# HHKBLite2BTwithoutArduinoFTDI.net
KiCad netlist of a schematic drawn in EAGLE
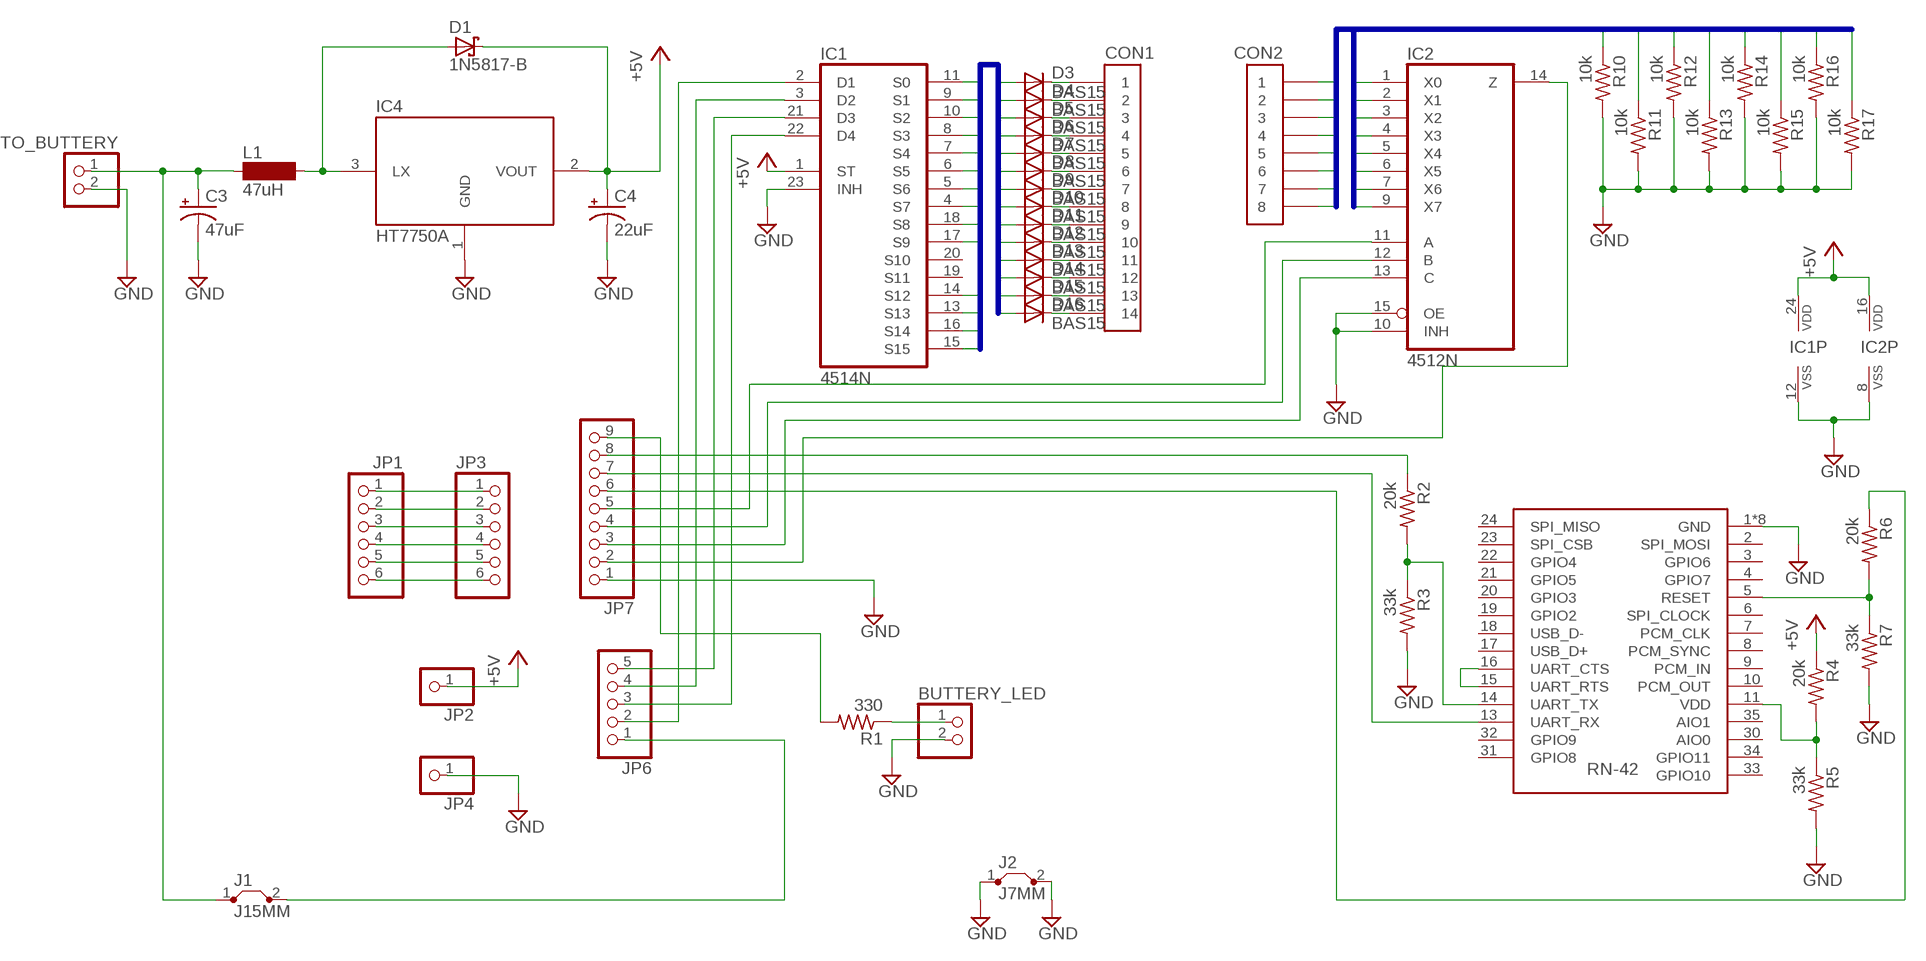
[diagram p0: schematic, sheet 1]

(export (version "E")
  (design (tool "Eeschema 10.0.6"))
  (components
    (comp (ref "BUTTERY_LED")
      (value "PINHD-1X2")
      (footprint "eagle-import:1X02")
      (libsource (lib "eagle-import") (part "PINHD-1X2"))
    )
    (comp (ref "C3")
      (value "47uF")
      (footprint "eagle-import:E5-10,5")
      (libsource (lib "eagle-import") (part "CPOL-USE5-10.5"))
    )
    (comp (ref "C4")
      (value "22uF")
      (footprint "eagle-import:E5-10,5")
      (libsource (lib "eagle-import") (part "CPOL-USE5-10.5"))
    )
    (comp (ref "CON1")
      (value "45045-1445")
      (footprint "eagle-import:52045-1445")
      (libsource (lib "eagle-import") (part "45045-1445"))
    )
    (comp (ref "CON2")
      (value "45045-0845")
      (footprint "eagle-import:52045-0845")
      (libsource (lib "eagle-import") (part "45045-0845"))
    )
    (comp (ref "D1")
      (value "1N5817-B")
      (footprint "eagle-import:DO41-7.6")
      (libsource (lib "eagle-import") (part "1N5817-B"))
    )
    (comp (ref "D3")
      (value "BAS15")
      (footprint "eagle-import:DO34-7")
      (libsource (lib "eagle-import") (part "BAS15"))
    )
    (comp (ref "D4")
      (value "BAS15")
      (footprint "eagle-import:DO34-7")
      (libsource (lib "eagle-import") (part "BAS15"))
    )
    (comp (ref "D5")
      (value "BAS15")
      (footprint "eagle-import:DO34-7")
      (libsource (lib "eagle-import") (part "BAS15"))
    )
    (comp (ref "D6")
      (value "BAS15")
      (footprint "eagle-import:DO34-7")
      (libsource (lib "eagle-import") (part "BAS15"))
    )
    (comp (ref "D7")
      (value "BAS15")
      (footprint "eagle-import:DO34-7")
      (libsource (lib "eagle-import") (part "BAS15"))
    )
    (comp (ref "D8")
      (value "BAS15")
      (footprint "eagle-import:DO34-7")
      (libsource (lib "eagle-import") (part "BAS15"))
    )
    (comp (ref "D9")
      (value "BAS15")
      (footprint "eagle-import:DO34-7")
      (libsource (lib "eagle-import") (part "BAS15"))
    )
    (comp (ref "D10")
      (value "BAS15")
      (footprint "eagle-import:DO34-7")
      (libsource (lib "eagle-import") (part "BAS15"))
    )
    (comp (ref "D11")
      (value "BAS15")
      (footprint "eagle-import:DO34-7")
      (libsource (lib "eagle-import") (part "BAS15"))
    )
    (comp (ref "D12")
      (value "BAS15")
      (footprint "eagle-import:DO34-7")
      (libsource (lib "eagle-import") (part "BAS15"))
    )
    (comp (ref "D13")
      (value "BAS15")
      (footprint "eagle-import:DO34-7")
      (libsource (lib "eagle-import") (part "BAS15"))
    )
    (comp (ref "D14")
      (value "BAS15")
      (footprint "eagle-import:DO34-7")
      (libsource (lib "eagle-import") (part "BAS15"))
    )
    (comp (ref "D15")
      (value "BAS15")
      (footprint "eagle-import:DO34-7")
      (libsource (lib "eagle-import") (part "BAS15"))
    )
    (comp (ref "D16")
      (value "BAS15")
      (footprint "eagle-import:DO34-7")
      (libsource (lib "eagle-import") (part "BAS15"))
    )
    (comp (ref "IC1")
      (value "4514N")
      (footprint "eagle-import:DIL24-6")
      (libsource (lib "eagle-import") (part "4514N"))
    )
    (comp (ref "IC2")
      (value "4512N")
      (footprint "eagle-import:DIL16")
      (libsource (lib "eagle-import") (part "4512N"))
    )
    (comp (ref "IC4")
      (value "HT7750A")
      (footprint "eagle-import:TO-92")
      (libsource (lib "eagle-import") (part "HT7750A"))
    )
    (comp (ref "J1")
      (value "J15MM")
      (footprint "eagle-import:15")
      (libsource (lib "eagle-import") (part "J15MM"))
    )
    (comp (ref "J2")
      (value "J7MM")
      (footprint "eagle-import:07")
      (libsource (lib "eagle-import") (part "J7MM"))
    )
    (comp (ref "JP1")
      (value "PINHD-1X6")
      (footprint "eagle-import:1X06")
      (libsource (lib "eagle-import") (part "PINHD-1X6"))
    )
    (comp (ref "JP2")
      (value "PINHD-1X1")
      (footprint "eagle-import:1X01")
      (libsource (lib "eagle-import") (part "PINHD-1X1"))
    )
    (comp (ref "JP3")
      (value "PINHD-1X6/90")
      (footprint "eagle-import:1X06_90")
      (libsource (lib "eagle-import") (part "PINHD-1X6/90"))
    )
    (comp (ref "JP4")
      (value "PINHD-1X1")
      (footprint "eagle-import:1X01")
      (libsource (lib "eagle-import") (part "PINHD-1X1"))
    )
    (comp (ref "JP6")
      (value "PINHD-1X5")
      (footprint "eagle-import:1X05")
      (libsource (lib "eagle-import") (part "PINHD-1X5"))
    )
    (comp (ref "JP7")
      (value "PINHD-1X9")
      (footprint "eagle-import:1X09")
      (libsource (lib "eagle-import") (part "PINHD-1X9"))
    )
    (comp (ref "L1")
      (value "47uH")
      (footprint "eagle-import:BS11")
      (libsource (lib "eagle-import") (part "BS11"))
    )
    (comp (ref "R1")
      (value "330")
      (footprint "eagle-import:0207_7")
      (libsource (lib "eagle-import") (part "R-US_0207/7"))
    )
    (comp (ref "R2")
      (value "20k")
      (footprint "eagle-import:0207_7")
      (libsource (lib "eagle-import") (part "R-US_0207/7"))
    )
    (comp (ref "R3")
      (value "33k")
      (footprint "eagle-import:0207_7")
      (libsource (lib "eagle-import") (part "R-US_0207/7"))
    )
    (comp (ref "R4")
      (value "20k")
      (footprint "eagle-import:0207_7")
      (libsource (lib "eagle-import") (part "R-US_0207/7"))
    )
    (comp (ref "R5")
      (value "33k")
      (footprint "eagle-import:0207_7")
      (libsource (lib "eagle-import") (part "R-US_0207/7"))
    )
    (comp (ref "R6")
      (value "20k")
      (footprint "eagle-import:0207_7")
      (libsource (lib "eagle-import") (part "R-US_0207/7"))
    )
    (comp (ref "R7")
      (value "33k")
      (footprint "eagle-import:0207_7")
      (libsource (lib "eagle-import") (part "R-US_0207/7"))
    )
    (comp (ref "R10")
      (value "10k")
      (footprint "eagle-import:0207_7")
      (libsource (lib "eagle-import") (part "R-US_0207/7"))
    )
    (comp (ref "R11")
      (value "10k")
      (footprint "eagle-import:0207_7")
      (libsource (lib "eagle-import") (part "R-US_0207/7"))
    )
    (comp (ref "R12")
      (value "10k")
      (footprint "eagle-import:0207_7")
      (libsource (lib "eagle-import") (part "R-US_0207/7"))
    )
    (comp (ref "R13")
      (value "10k")
      (footprint "eagle-import:0207_10")
      (libsource (lib "eagle-import") (part "resistor_R-US_0207/10"))
    )
    (comp (ref "R14")
      (value "10k")
      (footprint "eagle-import:0207_7")
      (libsource (lib "eagle-import") (part "R-US_0207/7"))
    )
    (comp (ref "R15")
      (value "10k")
      (footprint "eagle-import:0207_7")
      (libsource (lib "eagle-import") (part "R-US_0207/7"))
    )
    (comp (ref "R16")
      (value "10k")
      (footprint "eagle-import:0207_7")
      (libsource (lib "eagle-import") (part "R-US_0207/7"))
    )
    (comp (ref "R17")
      (value "10k")
      (footprint "eagle-import:0207_7")
      (libsource (lib "eagle-import") (part "R-US_0207/7"))
    )
    (comp (ref "TO_BUTTERY")
      (value "PINHD-1X2")
      (footprint "eagle-import:1X02")
      (libsource (lib "eagle-import") (part "PINHD-1X2"))
    )
    (comp (ref "U$1")
      (value "RN-42")
      (footprint "eagle-import:RN-42")
      (libsource (lib "eagle-import") (part "RN-42"))
    )
  )
  (nets
    (net (code "1") (name "+5V") (class "Default")
      (node (ref "C4") (pin "+") (pinfunction "+_+") (pintype "passive"))
      (node (ref "D1") (pin "C") (pinfunction "C_C") (pintype "passive"))
      (node (ref "IC1") (pin "1") (pinfunction "ST_1") (pintype "input"))
      (node (ref "IC1") (pin "24") (pinfunction "VDD_24") (pintype "power_in"))
      (node (ref "IC2") (pin "16") (pinfunction "VDD_16") (pintype "power_in"))
      (node (ref "IC4") (pin "2") (pinfunction "VOUT_2") (pintype "output"))
      (node (ref "JP2") (pin "1") (pinfunction "1_1") (pintype "passive"))
      (node (ref "R4") (pin "1") (pinfunction "1_1") (pintype "passive"))
    )
    (net (code "2") (name "/CON1BUS_O0") (class "Default")
      (node (ref "D3") (pin "A") (pinfunction "A_A") (pintype "passive"))
      (node (ref "IC1") (pin "11") (pinfunction "S0_11") (pintype "output"))
    )
    (net (code "3") (name "/CON1BUS_O1") (class "Default")
      (node (ref "D5") (pin "A") (pinfunction "A_A") (pintype "passive"))
      (node (ref "IC1") (pin "9") (pinfunction "S1_9") (pintype "output"))
    )
    (net (code "4") (name "/CON1BUS_O2") (class "Default")
      (node (ref "D4") (pin "A") (pinfunction "A_A") (pintype "passive"))
      (node (ref "IC1") (pin "10") (pinfunction "S2_10") (pintype "output"))
    )
    (net (code "5") (name "/CON1BUS_O3") (class "Default")
      (node (ref "D6") (pin "A") (pinfunction "A_A") (pintype "passive"))
      (node (ref "IC1") (pin "8") (pinfunction "S3_8") (pintype "output"))
    )
    (net (code "6") (name "/CON1BUS_O4") (class "Default")
      (node (ref "D7") (pin "A") (pinfunction "A_A") (pintype "passive"))
      (node (ref "IC1") (pin "7") (pinfunction "S4_7") (pintype "output"))
    )
    (net (code "7") (name "/CON1BUS_O5") (class "Default")
      (node (ref "D8") (pin "A") (pinfunction "A_A") (pintype "passive"))
      (node (ref "IC1") (pin "6") (pinfunction "S5_6") (pintype "output"))
    )
    (net (code "8") (name "/CON1BUS_O6") (class "Default")
      (node (ref "D9") (pin "A") (pinfunction "A_A") (pintype "passive"))
      (node (ref "IC1") (pin "5") (pinfunction "S6_5") (pintype "output"))
    )
    (net (code "9") (name "/CON1BUS_O7") (class "Default")
      (node (ref "D10") (pin "A") (pinfunction "A_A") (pintype "passive"))
      (node (ref "IC1") (pin "4") (pinfunction "S7_4") (pintype "output"))
    )
    (net (code "10") (name "/CON1BUS_O8") (class "Default")
      (node (ref "D11") (pin "A") (pinfunction "A_A") (pintype "passive"))
      (node (ref "IC1") (pin "18") (pinfunction "S8_18") (pintype "output"))
    )
    (net (code "11") (name "/CON1BUS_O9") (class "Default")
      (node (ref "D16") (pin "A") (pinfunction "A_A") (pintype "passive"))
      (node (ref "IC1") (pin "17") (pinfunction "S9_17") (pintype "output"))
    )
    (net (code "12") (name "/CON1BUS_O12") (class "Default")
      (node (ref "D13") (pin "A") (pinfunction "A_A") (pintype "passive"))
      (node (ref "IC1") (pin "14") (pinfunction "S12_14") (pintype "output"))
    )
    (net (code "13") (name "/CON1BUS_O13") (class "Default")
      (node (ref "D12") (pin "A") (pinfunction "A_A") (pintype "passive"))
      (node (ref "IC1") (pin "13") (pinfunction "S13_13") (pintype "output"))
    )
    (net (code "14") (name "/CON1BUS_O14") (class "Default")
      (node (ref "D15") (pin "A") (pinfunction "A_A") (pintype "passive"))
      (node (ref "IC1") (pin "16") (pinfunction "S14_16") (pintype "output"))
    )
    (net (code "15") (name "/CON1BUS_O15") (class "Default")
      (node (ref "D14") (pin "A") (pinfunction "A_A") (pintype "passive"))
      (node (ref "IC1") (pin "15") (pinfunction "S15_15") (pintype "output"))
    )
    (net (code "16") (name "/CON2BUS_D0") (class "Default")
      (node (ref "CON2") (pin "8") (pinfunction "8_8") (pintype "bidirectional"))
      (node (ref "IC2") (pin "1") (pinfunction "X0_1") (pintype "input"))
      (node (ref "R10") (pin "1") (pinfunction "1_1") (pintype "passive"))
    )
    (net (code "17") (name "/CON2BUS_D1") (class "Default")
      (node (ref "CON2") (pin "7") (pinfunction "7_7") (pintype "bidirectional"))
      (node (ref "IC2") (pin "2") (pinfunction "X1_2") (pintype "input"))
      (node (ref "R11") (pin "1") (pinfunction "1_1") (pintype "passive"))
    )
    (net (code "18") (name "/CON2BUS_D2") (class "Default")
      (node (ref "CON2") (pin "6") (pinfunction "6_6") (pintype "bidirectional"))
      (node (ref "IC2") (pin "3") (pinfunction "X2_3") (pintype "input"))
      (node (ref "R12") (pin "1") (pinfunction "1_1") (pintype "passive"))
    )
    (net (code "19") (name "/CON2BUS_D3") (class "Default")
      (node (ref "CON2") (pin "5") (pinfunction "5_5") (pintype "bidirectional"))
      (node (ref "IC2") (pin "4") (pinfunction "X3_4") (pintype "input"))
      (node (ref "R13") (pin "1") (pinfunction "1_1") (pintype "passive"))
    )
    (net (code "20") (name "/CON2BUS_D4") (class "Default")
      (node (ref "CON2") (pin "4") (pinfunction "4_4") (pintype "bidirectional"))
      (node (ref "IC2") (pin "5") (pinfunction "X4_5") (pintype "input"))
      (node (ref "R14") (pin "1") (pinfunction "1_1") (pintype "passive"))
    )
    (net (code "21") (name "/CON2BUS_D5") (class "Default")
      (node (ref "CON2") (pin "3") (pinfunction "3_3") (pintype "bidirectional"))
      (node (ref "IC2") (pin "6") (pinfunction "X5_6") (pintype "input"))
      (node (ref "R15") (pin "1") (pinfunction "1_1") (pintype "passive"))
    )
    (net (code "22") (name "/CON2BUS_D6") (class "Default")
      (node (ref "CON2") (pin "2") (pinfunction "2_2") (pintype "bidirectional"))
      (node (ref "IC2") (pin "7") (pinfunction "X6_7") (pintype "input"))
      (node (ref "R16") (pin "1") (pinfunction "1_1") (pintype "passive"))
    )
    (net (code "23") (name "/CON2BUS_D7") (class "Default")
      (node (ref "CON2") (pin "1") (pinfunction "1_1") (pintype "bidirectional"))
      (node (ref "IC2") (pin "9") (pinfunction "X7_9") (pintype "input"))
      (node (ref "R17") (pin "1") (pinfunction "1_1") (pintype "passive"))
    )
    (net (code "24") (name "GND") (class "Default")
      (node (ref "BUTTERY_LED") (pin "2") (pinfunction "2_2") (pintype "passive"))
      (node (ref "C3") (pin "-") (pinfunction "-_-") (pintype "passive"))
      (node (ref "C4") (pin "-") (pinfunction "-_-") (pintype "passive"))
      (node (ref "IC1") (pin "12") (pinfunction "VSS_12") (pintype "power_in"))
      (node (ref "IC1") (pin "23") (pinfunction "INH_23") (pintype "input"))
      (node (ref "IC2") (pin "10") (pinfunction "INH_10") (pintype "input"))
      (node (ref "IC2") (pin "15") (pinfunction "OE_15") (pintype "input"))
      (node (ref "IC2") (pin "8") (pinfunction "VSS_8") (pintype "power_in"))
      (node (ref "IC4") (pin "1") (pinfunction "GND_1") (pintype "power_in"))
      (node (ref "J2") (pin "1") (pinfunction "1_1") (pintype "passive"))
      (node (ref "J2") (pin "2") (pinfunction "2_2") (pintype "passive"))
      (node (ref "JP4") (pin "1") (pinfunction "1_1") (pintype "passive"))
      (node (ref "JP7") (pin "1") (pinfunction "1_1") (pintype "passive"))
      (node (ref "R10") (pin "2") (pinfunction "2_2") (pintype "passive"))
      (node (ref "R11") (pin "2") (pinfunction "2_2") (pintype "passive"))
      (node (ref "R12") (pin "2") (pinfunction "2_2") (pintype "passive"))
      (node (ref "R13") (pin "2") (pinfunction "2_2") (pintype "passive"))
      (node (ref "R14") (pin "2") (pinfunction "2_2") (pintype "passive"))
      (node (ref "R15") (pin "2") (pinfunction "2_2") (pintype "passive"))
      (node (ref "R16") (pin "2") (pinfunction "2_2") (pintype "passive"))
      (node (ref "R17") (pin "2") (pinfunction "2_2") (pintype "passive"))
      (node (ref "R3") (pin "2") (pinfunction "2_2") (pintype "passive"))
      (node (ref "R5") (pin "2") (pinfunction "2_2") (pintype "passive"))
      (node (ref "R7") (pin "2") (pinfunction "2_2") (pintype "passive"))
      (node (ref "TO_BUTTERY") (pin "2") (pinfunction "2_2") (pintype "passive"))
      (node (ref "U$1") (pin "1") (pinfunction "GND_1") (pintype "power_in"))
      (node (ref "U$1") (pin "12") (pinfunction "GND_12") (pintype "power_in"))
      (node (ref "U$1") (pin "28") (pinfunction "GND_28") (pintype "power_in"))
      (node (ref "U$1") (pin "29") (pinfunction "GND_29") (pintype "power_in"))
      (node (ref "U$1") (pin "GND1") (pinfunction "GND_GND1") (pintype "power_in"))
      (node (ref "U$1") (pin "GND2") (pinfunction "GND_GND2") (pintype "power_in"))
      (node (ref "U$1") (pin "GND3") (pinfunction "GND_GND3") (pintype "power_in"))
      (node (ref "U$1") (pin "GND4") (pinfunction "GND_GND4") (pintype "power_in"))
    )
    (net (code "25") (name "Net-(BUTTERY_LED-Pad1)") (class "Default")
      (node (ref "BUTTERY_LED") (pin "1") (pinfunction "1_1") (pintype "passive"))
      (node (ref "R1") (pin "1") (pinfunction "1_1") (pintype "passive"))
    )
    (net (code "26") (name "Net-(C3-Pad+)") (class "Default")
      (node (ref "C3") (pin "+") (pinfunction "+_+") (pintype "passive"))
      (node (ref "J1") (pin "1") (pinfunction "1_1") (pintype "passive"))
      (node (ref "L1") (pin "1") (pinfunction "1_1") (pintype "passive"))
      (node (ref "TO_BUTTERY") (pin "1") (pinfunction "1_1") (pintype "passive"))
    )
    (net (code "27") (name "Net-(CON1-Pad1)") (class "Default")
      (node (ref "CON1") (pin "1") (pinfunction "1_1") (pintype "bidirectional"))
      (node (ref "D3") (pin "C") (pinfunction "C_C") (pintype "passive"))
    )
    (net (code "28") (name "Net-(CON1-Pad2)") (class "Default")
      (node (ref "CON1") (pin "2") (pinfunction "2_2") (pintype "bidirectional"))
      (node (ref "D4") (pin "C") (pinfunction "C_C") (pintype "passive"))
    )
    (net (code "29") (name "Net-(CON1-Pad3)") (class "Default")
      (node (ref "CON1") (pin "3") (pinfunction "3_3") (pintype "bidirectional"))
      (node (ref "D5") (pin "C") (pinfunction "C_C") (pintype "passive"))
    )
    (net (code "30") (name "Net-(CON1-Pad4)") (class "Default")
      (node (ref "CON1") (pin "4") (pinfunction "4_4") (pintype "bidirectional"))
      (node (ref "D6") (pin "C") (pinfunction "C_C") (pintype "passive"))
    )
    (net (code "31") (name "Net-(CON1-Pad5)") (class "Default")
      (node (ref "CON1") (pin "5") (pinfunction "5_5") (pintype "bidirectional"))
      (node (ref "D7") (pin "C") (pinfunction "C_C") (pintype "passive"))
    )
    (net (code "32") (name "Net-(CON1-Pad6)") (class "Default")
      (node (ref "CON1") (pin "6") (pinfunction "6_6") (pintype "bidirectional"))
      (node (ref "D8") (pin "C") (pinfunction "C_C") (pintype "passive"))
    )
    (net (code "33") (name "Net-(CON1-Pad7)") (class "Default")
      (node (ref "CON1") (pin "7") (pinfunction "7_7") (pintype "bidirectional"))
      (node (ref "D9") (pin "C") (pinfunction "C_C") (pintype "passive"))
    )
    (net (code "34") (name "Net-(CON1-Pad8)") (class "Default")
      (node (ref "CON1") (pin "8") (pinfunction "8_8") (pintype "bidirectional"))
      (node (ref "D10") (pin "C") (pinfunction "C_C") (pintype "passive"))
    )
    (net (code "35") (name "Net-(CON1-Pad9)") (class "Default")
      (node (ref "CON1") (pin "9") (pinfunction "9_9") (pintype "bidirectional"))
      (node (ref "D11") (pin "C") (pinfunction "C_C") (pintype "passive"))
    )
    (net (code "36") (name "Net-(CON1-Pad10)") (class "Default")
      (node (ref "CON1") (pin "10") (pinfunction "10_10") (pintype "bidirectional"))
      (node (ref "D12") (pin "C") (pinfunction "C_C") (pintype "passive"))
    )
    (net (code "37") (name "Net-(CON1-Pad11)") (class "Default")
      (node (ref "CON1") (pin "11") (pinfunction "11_11") (pintype "bidirectional"))
      (node (ref "D13") (pin "C") (pinfunction "C_C") (pintype "passive"))
    )
    (net (code "38") (name "Net-(CON1-Pad12)") (class "Default")
      (node (ref "CON1") (pin "12") (pinfunction "12_12") (pintype "bidirectional"))
      (node (ref "D14") (pin "C") (pinfunction "C_C") (pintype "passive"))
    )
    (net (code "39") (name "Net-(CON1-Pad13)") (class "Default")
      (node (ref "CON1") (pin "13") (pinfunction "13_13") (pintype "bidirectional"))
      (node (ref "D15") (pin "C") (pinfunction "C_C") (pintype "passive"))
    )
    (net (code "40") (name "Net-(CON1-Pad14)") (class "Default")
      (node (ref "CON1") (pin "14") (pinfunction "14_14") (pintype "bidirectional"))
      (node (ref "D16") (pin "C") (pinfunction "C_C") (pintype "passive"))
    )
    (net (code "41") (name "Net-(IC1A-D1)") (class "Default")
      (node (ref "IC1") (pin "2") (pinfunction "D1_2") (pintype "input"))
      (node (ref "JP6") (pin "2") (pinfunction "2_2") (pintype "passive"))
    )
    (net (code "42") (name "Net-(IC1A-D2)") (class "Default")
      (node (ref "IC1") (pin "3") (pinfunction "D2_3") (pintype "input"))
      (node (ref "JP6") (pin "4") (pinfunction "4_4") (pintype "passive"))
    )
    (net (code "43") (name "Net-(IC1A-D3)") (class "Default")
      (node (ref "IC1") (pin "21") (pinfunction "D3_21") (pintype "input"))
      (node (ref "JP6") (pin "5") (pinfunction "5_5") (pintype "passive"))
    )
    (net (code "44") (name "Net-(IC1A-D4)") (class "Default")
      (node (ref "IC1") (pin "22") (pinfunction "D4_22") (pintype "input"))
      (node (ref "JP6") (pin "3") (pinfunction "3_3") (pintype "passive"))
    )
    (net (code "45") (name "Net-(IC2A-A)") (class "Default")
      (node (ref "IC2") (pin "11") (pinfunction "A_11") (pintype "input"))
      (node (ref "JP7") (pin "5") (pinfunction "5_5") (pintype "passive"))
    )
    (net (code "46") (name "Net-(IC2A-B)") (class "Default")
      (node (ref "IC2") (pin "12") (pinfunction "B_12") (pintype "input"))
      (node (ref "JP7") (pin "4") (pinfunction "4_4") (pintype "passive"))
    )
    (net (code "47") (name "Net-(IC2A-C)") (class "Default")
      (node (ref "IC2") (pin "13") (pinfunction "C_13") (pintype "input"))
      (node (ref "JP7") (pin "3") (pinfunction "3_3") (pintype "passive"))
    )
    (net (code "48") (name "Net-(IC2A-Z)") (class "Default")
      (node (ref "IC2") (pin "14") (pinfunction "Z_14") (pintype "tri_state"))
      (node (ref "JP7") (pin "2") (pinfunction "2_2") (pintype "passive"))
    )
    (net (code "49") (name "Net-(IC4-LX)") (class "Default")
      (node (ref "D1") (pin "A") (pinfunction "A_A") (pintype "passive"))
      (node (ref "IC4") (pin "3") (pinfunction "LX_3") (pintype "input"))
      (node (ref "L1") (pin "2") (pinfunction "2_2") (pintype "passive"))
    )
    (net (code "50") (name "Net-(J1-Pad2)") (class "Default")
      (node (ref "J1") (pin "2") (pinfunction "2_2") (pintype "passive"))
      (node (ref "JP6") (pin "1") (pinfunction "1_1") (pintype "passive"))
    )
    (net (code "51") (name "Net-(JP1-Pad1)") (class "Default")
      (node (ref "JP1") (pin "1") (pinfunction "1_1") (pintype "passive"))
      (node (ref "JP3") (pin "1") (pinfunction "1_1") (pintype "passive"))
    )
    (net (code "52") (name "Net-(JP1-Pad2)") (class "Default")
      (node (ref "JP1") (pin "2") (pinfunction "2_2") (pintype "passive"))
      (node (ref "JP3") (pin "2") (pinfunction "2_2") (pintype "passive"))
    )
    (net (code "53") (name "Net-(JP1-Pad3)") (class "Default")
      (node (ref "JP1") (pin "3") (pinfunction "3_3") (pintype "passive"))
      (node (ref "JP3") (pin "3") (pinfunction "3_3") (pintype "passive"))
    )
    (net (code "54") (name "Net-(JP1-Pad4)") (class "Default")
      (node (ref "JP1") (pin "4") (pinfunction "4_4") (pintype "passive"))
      (node (ref "JP3") (pin "4") (pinfunction "4_4") (pintype "passive"))
    )
    (net (code "55") (name "Net-(JP1-Pad5)") (class "Default")
      (node (ref "JP1") (pin "5") (pinfunction "5_5") (pintype "passive"))
      (node (ref "JP3") (pin "5") (pinfunction "5_5") (pintype "passive"))
    )
    (net (code "56") (name "Net-(JP1-Pad6)") (class "Default")
      (node (ref "JP1") (pin "6") (pinfunction "6_6") (pintype "passive"))
      (node (ref "JP3") (pin "6") (pinfunction "6_6") (pintype "passive"))
    )
    (net (code "57") (name "Net-(JP7-Pad6)") (class "Default")
      (node (ref "JP7") (pin "6") (pinfunction "6_6") (pintype "passive"))
      (node (ref "R6") (pin "1") (pinfunction "1_1") (pintype "passive"))
    )
    (net (code "58") (name "Net-(JP7-Pad8)") (class "Default")
      (node (ref "JP7") (pin "8") (pinfunction "8_8") (pintype "passive"))
      (node (ref "R2") (pin "1") (pinfunction "1_1") (pintype "passive"))
    )
    (net (code "59") (name "Net-(JP7-Pad9)") (class "Default")
      (node (ref "JP7") (pin "9") (pinfunction "9_9") (pintype "passive"))
      (node (ref "R1") (pin "2") (pinfunction "2_2") (pintype "passive"))
    )
    (net (code "60") (name "Net-(U$1-RESET)") (class "Default")
      (node (ref "R6") (pin "2") (pinfunction "2_2") (pintype "passive"))
      (node (ref "R7") (pin "1") (pinfunction "1_1") (pintype "passive"))
      (node (ref "U$1") (pin "5") (pinfunction "RESET_5") (pintype "bidirectional"))
    )
    (net (code "61") (name "Net-(U$1-UART_CTS)") (class "Default")
      (node (ref "U$1") (pin "15") (pinfunction "UART_RTS_15") (pintype "bidirectional"))
      (node (ref "U$1") (pin "16") (pinfunction "UART_CTS_16") (pintype "bidirectional"))
    )
    (net (code "62") (name "Net-(U$1-UART_RX)") (class "Default")
      (node (ref "JP7") (pin "7") (pinfunction "7_7") (pintype "passive"))
      (node (ref "U$1") (pin "13") (pinfunction "UART_RX_13") (pintype "bidirectional"))
    )
    (net (code "63") (name "Net-(U$1-UART_TX)") (class "Default")
      (node (ref "R2") (pin "2") (pinfunction "2_2") (pintype "passive"))
      (node (ref "R3") (pin "1") (pinfunction "1_1") (pintype "passive"))
      (node (ref "U$1") (pin "14") (pinfunction "UART_TX_14") (pintype "bidirectional"))
    )
    (net (code "64") (name "Net-(U$1-VDD)") (class "Default")
      (node (ref "R4") (pin "2") (pinfunction "2_2") (pintype "passive"))
      (node (ref "R5") (pin "1") (pinfunction "1_1") (pintype "passive"))
      (node (ref "U$1") (pin "11") (pinfunction "VDD_11") (pintype "power_in"))
    )
    (net (code "65") (name "unconnected-(IC1A-S10-Pad20)") (class "Default")
      (node (ref "IC1") (pin "20") (pinfunction "S10_20") (pintype "output"))
    )
    (net (code "66") (name "unconnected-(IC1A-S11-Pad19)") (class "Default")
      (node (ref "IC1") (pin "19") (pinfunction "S11_19") (pintype "output"))
    )
    (net (code "67") (name "unconnected-(U$1-AIO0-Pad30)") (class "Default")
      (node (ref "U$1") (pin "30") (pinfunction "AIO0_30") (pintype "bidirectional"))
    )
    (net (code "68") (name "unconnected-(U$1-AIO1-Pad35)") (class "Default")
      (node (ref "U$1") (pin "35") (pinfunction "AIO1_35") (pintype "bidirectional"))
    )
    (net (code "69") (name "unconnected-(U$1-GPIO2-Pad19)") (class "Default")
      (node (ref "U$1") (pin "19") (pinfunction "GPIO2_19") (pintype "bidirectional"))
    )
    (net (code "70") (name "unconnected-(U$1-GPIO3-Pad20)") (class "Default")
      (node (ref "U$1") (pin "20") (pinfunction "GPIO3_20") (pintype "bidirectional"))
    )
    (net (code "71") (name "unconnected-(U$1-GPIO4-Pad22)") (class "Default")
      (node (ref "U$1") (pin "22") (pinfunction "GPIO4_22") (pintype "bidirectional"))
    )
    (net (code "72") (name "unconnected-(U$1-GPIO5-Pad21)") (class "Default")
      (node (ref "U$1") (pin "21") (pinfunction "GPIO5_21") (pintype "bidirectional"))
    )
    (net (code "73") (name "unconnected-(U$1-GPIO6-Pad3)") (class "Default")
      (node (ref "U$1") (pin "3") (pinfunction "GPIO6_3") (pintype "bidirectional"))
    )
    (net (code "74") (name "unconnected-(U$1-GPIO7-Pad4)") (class "Default")
      (node (ref "U$1") (pin "4") (pinfunction "GPIO7_4") (pintype "bidirectional"))
    )
    (net (code "75") (name "unconnected-(U$1-GPIO8-Pad31)") (class "Default")
      (node (ref "U$1") (pin "31") (pinfunction "GPIO8_31") (pintype "bidirectional"))
    )
    (net (code "76") (name "unconnected-(U$1-GPIO9-Pad32)") (class "Default")
      (node (ref "U$1") (pin "32") (pinfunction "GPIO9_32") (pintype "bidirectional"))
    )
    (net (code "77") (name "unconnected-(U$1-GPIO10-Pad33)") (class "Default")
      (node (ref "U$1") (pin "33") (pinfunction "GPIO10_33") (pintype "bidirectional"))
    )
    (net (code "78") (name "unconnected-(U$1-GPIO11-Pad34)") (class "Default")
      (node (ref "U$1") (pin "34") (pinfunction "GPIO11_34") (pintype "bidirectional"))
    )
    (net (code "79") (name "unconnected-(U$1-PCM_CLK-Pad7)") (class "Default")
      (node (ref "U$1") (pin "7") (pinfunction "PCM_CLK_7") (pintype "bidirectional"))
    )
    (net (code "80") (name "unconnected-(U$1-PCM_IN-Pad9)") (class "Default")
      (node (ref "U$1") (pin "9") (pinfunction "PCM_IN_9") (pintype "bidirectional"))
    )
    (net (code "81") (name "unconnected-(U$1-PCM_OUT-Pad10)") (class "Default")
      (node (ref "U$1") (pin "10") (pinfunction "PCM_OUT_10") (pintype "bidirectional"))
    )
    (net (code "82") (name "unconnected-(U$1-PCM_SYNC-Pad8)") (class "Default")
      (node (ref "U$1") (pin "8") (pinfunction "PCM_SYNC_8") (pintype "bidirectional"))
    )
    (net (code "83") (name "unconnected-(U$1-SPI_CLOCK-Pad6)") (class "Default")
      (node (ref "U$1") (pin "6") (pinfunction "SPI_CLOCK_6") (pintype "bidirectional"))
    )
    (net (code "84") (name "unconnected-(U$1-SPI_CSB-Pad23)") (class "Default")
      (node (ref "U$1") (pin "23") (pinfunction "SPI_CSB_23") (pintype "bidirectional"))
    )
    (net (code "85") (name "unconnected-(U$1-SPI_MISO-Pad24)") (class "Default")
      (node (ref "U$1") (pin "24") (pinfunction "SPI_MISO_24") (pintype "bidirectional"))
    )
    (net (code "86") (name "unconnected-(U$1-SPI_MOSI-Pad2)") (class "Default")
      (node (ref "U$1") (pin "2") (pinfunction "SPI_MOSI_2") (pintype "bidirectional"))
    )
    (net (code "87") (name "unconnected-(U$1-USB_D+-Pad17)") (class "Default")
      (node (ref "U$1") (pin "17") (pinfunction "USB_D+_17") (pintype "bidirectional"))
    )
    (net (code "88") (name "unconnected-(U$1-USB_D--Pad18)") (class "Default")
      (node (ref "U$1") (pin "18") (pinfunction "USB_D-_18") (pintype "bidirectional"))
    )
  )
)
